# DistanceSensors.net
KiCad netlist of a schematic drawn in Altium Designer
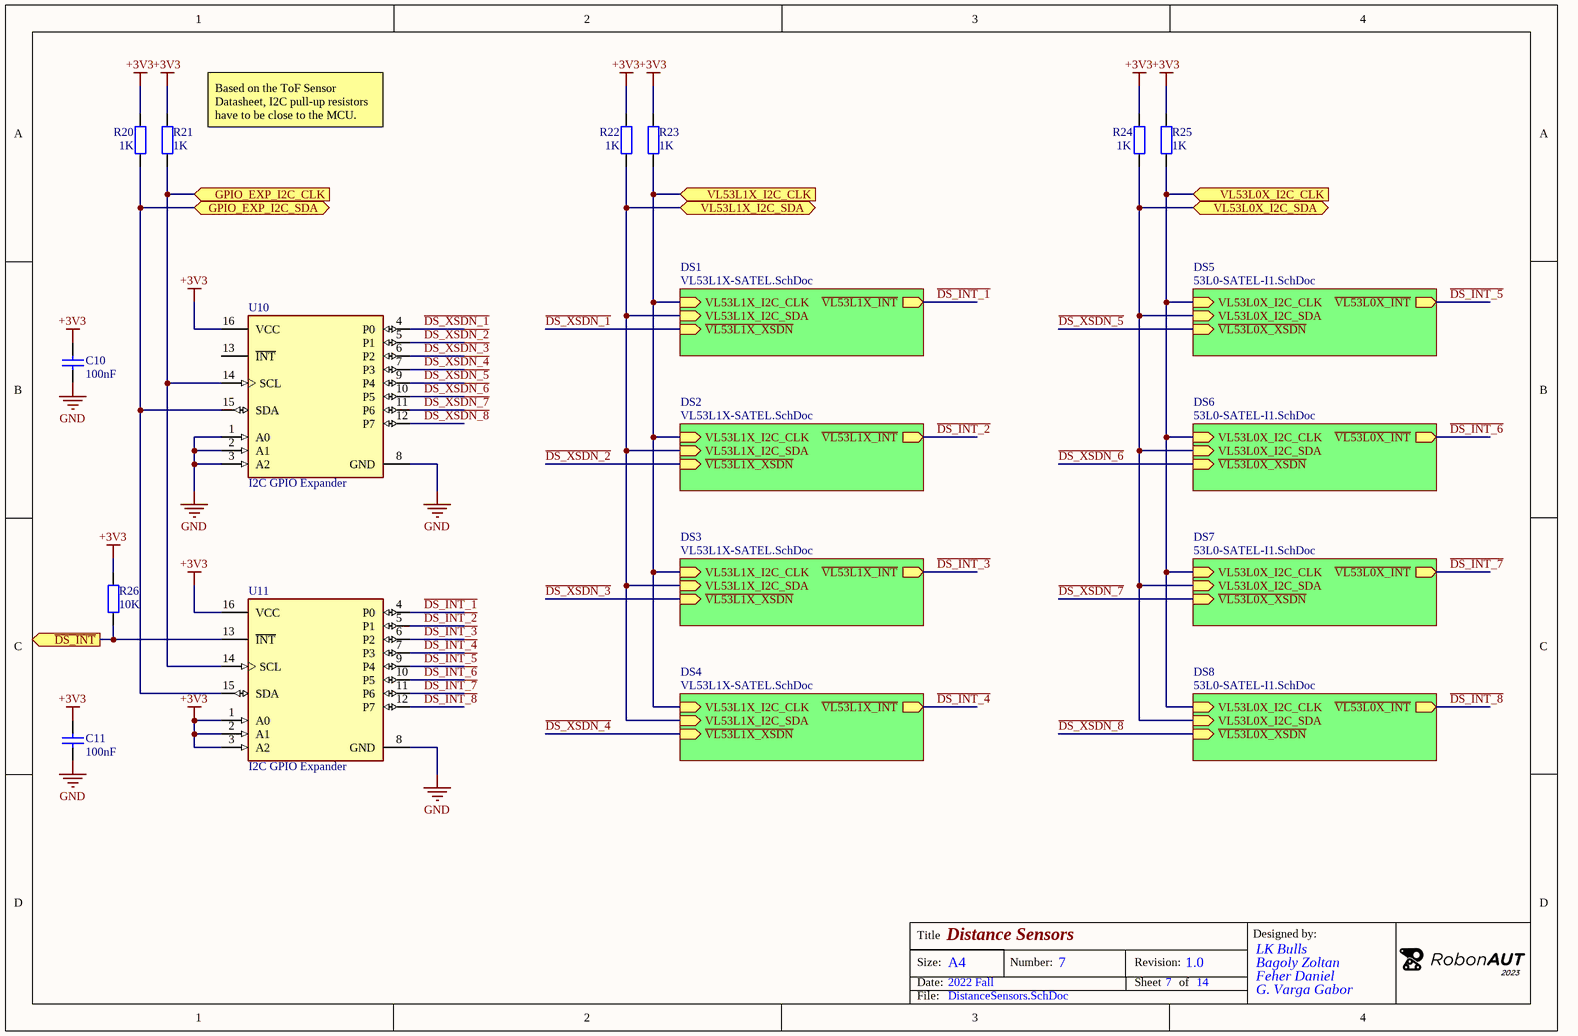
[diagram p0: DistanceSensors.SchDoc]

(export (version "E")
  (design (tool "Eeschema 10.0.6"))
  (components
    (comp (ref "C10")
      (value "100nF")
      (footprint "FP_0805_CAP_085")
      (description "Capacitor")
      (fields (field (name "TOLERANCE") "10%") (field (name "VOLTAGE") "50V"))
      (libsource (lib "LKBulls2023") (part "CAP"))
    )
    (comp (ref "C11")
      (value "100nF")
      (footprint "FP_0805_CAP_085")
      (description "Capacitor")
      (fields (field (name "TOLERANCE") "10%") (field (name "VOLTAGE") "50V"))
      (libsource (lib "LKBulls2023") (part "CAP"))
    )
    (comp (ref "R20")
      (value "1K")
      (footprint "FP_0805_RES")
      (description "Resistor")
      (fields (field (name "TOLERANCE") "5%") (field (name "POWER") "0.125W"))
      (libsource (lib "LKBulls2023") (part "RES"))
    )
    (comp (ref "R21")
      (value "1K")
      (footprint "FP_0805_RES")
      (description "Resistor")
      (fields (field (name "TOLERANCE") "5%") (field (name "POWER") "0.125W"))
      (libsource (lib "LKBulls2023") (part "RES"))
    )
    (comp (ref "R22")
      (value "1K")
      (footprint "FP_0805_RES")
      (description "Resistor")
      (fields (field (name "TOLERANCE") "5%") (field (name "POWER") "0.125W"))
      (libsource (lib "LKBulls2023") (part "RES"))
    )
    (comp (ref "R23")
      (value "1K")
      (footprint "FP_0805_RES")
      (description "Resistor")
      (fields (field (name "TOLERANCE") "5%") (field (name "POWER") "0.125W"))
      (libsource (lib "LKBulls2023") (part "RES"))
    )
    (comp (ref "R24")
      (value "1K")
      (footprint "FP_0805_RES")
      (description "Resistor")
      (fields (field (name "TOLERANCE") "5%") (field (name "POWER") "0.125W"))
      (libsource (lib "LKBulls2023") (part "RES"))
    )
    (comp (ref "R25")
      (value "1K")
      (footprint "FP_0805_RES")
      (description "Resistor")
      (fields (field (name "TOLERANCE") "5%") (field (name "POWER") "0.125W"))
      (libsource (lib "LKBulls2023") (part "RES"))
    )
    (comp (ref "R26")
      (value "10K")
      (footprint "FP_0805_RES")
      (description "Resistor")
      (fields (field (name "TOLERANCE") "5%") (field (name "POWER") "0.125W"))
      (libsource (lib "LKBulls2023") (part "RES"))
    )
    (comp (ref "U10")
      (value "I2C GPIO Expander")
      (footprint "FP_TCA9534PWR")
      (description "I2C/SMBus Interface 100kHz/400kHz 5.5V 16-Pin TSSOP T/R")
      (fields
        (field (name "MANUFACTURER") "Texas Instruments")
        (field (name "MANUFACTURER PART NUMBER") "TCA9534PWR")
      )
      (libsource (lib "LKBulls2023") (part "TCA9534PWR"))
    )
    (comp (ref "U11")
      (value "I2C GPIO Expander")
      (footprint "FP_TCA9534PWR")
      (description "I2C/SMBus Interface 100kHz/400kHz 5.5V 16-Pin TSSOP T/R")
      (fields
        (field (name "MANUFACTURER") "Texas Instruments")
        (field (name "MANUFACTURER PART NUMBER") "TCA9534PWR")
      )
      (libsource (lib "LKBulls2023") (part "TCA9534PWR"))
    )
  )
  (nets
    (net (code "1") (name "+3V3") (class "Default")
      (node (ref "C10") (pin "2") (pinfunction "2_2") (pintype "passive"))
      (node (ref "C11") (pin "2") (pinfunction "2_2") (pintype "passive"))
      (node (ref "R20") (pin "2") (pinfunction "2_2") (pintype "passive"))
      (node (ref "R21") (pin "2") (pinfunction "2_2") (pintype "passive"))
      (node (ref "R22") (pin "2") (pinfunction "2_2") (pintype "passive"))
      (node (ref "R23") (pin "2") (pinfunction "2_2") (pintype "passive"))
      (node (ref "R24") (pin "2") (pinfunction "2_2") (pintype "passive"))
      (node (ref "R25") (pin "2") (pinfunction "2_2") (pintype "passive"))
      (node (ref "R26") (pin "2") (pinfunction "2_2") (pintype "passive"))
      (node (ref "U10") (pin "16") (pinfunction "VCC_16") (pintype "power_in"))
      (node (ref "U11") (pin "1") (pinfunction "A0_1") (pintype "input"))
      (node (ref "U11") (pin "16") (pinfunction "VCC_16") (pintype "power_in"))
      (node (ref "U11") (pin "2") (pinfunction "A1_2") (pintype "input"))
      (node (ref "U11") (pin "3") (pinfunction "A2_3") (pintype "input"))
    )
    (net (code "2") (name "/GPIO_EXP_I2C_CLK") (class "Default")
      (node (ref "R21") (pin "1") (pinfunction "1_1") (pintype "passive"))
      (node (ref "U10") (pin "14") (pinfunction "SCL_14") (pintype "input"))
      (node (ref "U11") (pin "14") (pinfunction "SCL_14") (pintype "input"))
    )
    (net (code "3") (name "/GPIO_EXP_I2C_SDA") (class "Default")
      (node (ref "R20") (pin "1") (pinfunction "1_1") (pintype "passive"))
      (node (ref "U10") (pin "15") (pinfunction "SDA_15") (pintype "bidirectional"))
      (node (ref "U11") (pin "15") (pinfunction "SDA_15") (pintype "bidirectional"))
    )
    (net (code "4") (name "/VL53L0X_I2C_CLK") (class "Default")
      (node (ref "R25") (pin "1") (pinfunction "1_1") (pintype "passive"))
    )
    (net (code "5") (name "/VL53L0X_I2C_SDA") (class "Default")
      (node (ref "R24") (pin "1") (pinfunction "1_1") (pintype "passive"))
    )
    (net (code "6") (name "/VL53L1X_I2C_CLK") (class "Default")
      (node (ref "R23") (pin "1") (pinfunction "1_1") (pintype "passive"))
    )
    (net (code "7") (name "/VL53L1X_I2C_SDA") (class "Default")
      (node (ref "R22") (pin "1") (pinfunction "1_1") (pintype "passive"))
    )
    (net (code "8") (name "/~{DS_INT_1}") (class "Default")
      (node (ref "U11") (pin "4") (pinfunction "P0_4") (pintype "bidirectional"))
    )
    (net (code "9") (name "/~{DS_INT_2}") (class "Default")
      (node (ref "U11") (pin "5") (pinfunction "P1_5") (pintype "bidirectional"))
    )
    (net (code "10") (name "/~{DS_INT_3}") (class "Default")
      (node (ref "U11") (pin "6") (pinfunction "P2_6") (pintype "bidirectional"))
    )
    (net (code "11") (name "/~{DS_INT_4}") (class "Default")
      (node (ref "U11") (pin "7") (pinfunction "P3_7") (pintype "bidirectional"))
    )
    (net (code "12") (name "/~{DS_INT_5}") (class "Default")
      (node (ref "U11") (pin "9") (pinfunction "P4_9") (pintype "bidirectional"))
    )
    (net (code "13") (name "/~{DS_INT_6}") (class "Default")
      (node (ref "U11") (pin "10") (pinfunction "P5_10") (pintype "bidirectional"))
    )
    (net (code "14") (name "/~{DS_INT_7}") (class "Default")
      (node (ref "U11") (pin "11") (pinfunction "P6_11") (pintype "bidirectional"))
    )
    (net (code "15") (name "/~{DS_INT_8}") (class "Default")
      (node (ref "U11") (pin "12") (pinfunction "P7_12") (pintype "bidirectional"))
    )
    (net (code "16") (name "/~{DS_INT}") (class "Default")
      (node (ref "R26") (pin "1") (pinfunction "1_1") (pintype "passive"))
      (node (ref "U11") (pin "13") (pinfunction "~{INT}_13") (pintype "open_collector"))
    )
    (net (code "17") (name "/~{DS_XSDN_1}") (class "Default")
      (node (ref "U10") (pin "4") (pinfunction "P0_4") (pintype "bidirectional"))
    )
    (net (code "18") (name "/~{DS_XSDN_2}") (class "Default")
      (node (ref "U10") (pin "5") (pinfunction "P1_5") (pintype "bidirectional"))
    )
    (net (code "19") (name "/~{DS_XSDN_3}") (class "Default")
      (node (ref "U10") (pin "6") (pinfunction "P2_6") (pintype "bidirectional"))
    )
    (net (code "20") (name "/~{DS_XSDN_4}") (class "Default")
      (node (ref "U10") (pin "7") (pinfunction "P3_7") (pintype "bidirectional"))
    )
    (net (code "21") (name "/~{DS_XSDN_5}") (class "Default")
      (node (ref "U10") (pin "9") (pinfunction "P4_9") (pintype "bidirectional"))
    )
    (net (code "22") (name "/~{DS_XSDN_6}") (class "Default")
      (node (ref "U10") (pin "10") (pinfunction "P5_10") (pintype "bidirectional"))
    )
    (net (code "23") (name "/~{DS_XSDN_7}") (class "Default")
      (node (ref "U10") (pin "11") (pinfunction "P6_11") (pintype "bidirectional"))
    )
    (net (code "24") (name "/~{DS_XSDN_8}") (class "Default")
      (node (ref "U10") (pin "12") (pinfunction "P7_12") (pintype "bidirectional"))
    )
    (net (code "25") (name "GND") (class "Default")
      (node (ref "C10") (pin "1") (pinfunction "1_1") (pintype "passive"))
      (node (ref "C11") (pin "1") (pinfunction "1_1") (pintype "passive"))
      (node (ref "U10") (pin "1") (pinfunction "A0_1") (pintype "input"))
      (node (ref "U10") (pin "2") (pinfunction "A1_2") (pintype "input"))
      (node (ref "U10") (pin "3") (pinfunction "A2_3") (pintype "input"))
      (node (ref "U10") (pin "8") (pinfunction "GND_8") (pintype "power_in"))
      (node (ref "U11") (pin "8") (pinfunction "GND_8") (pintype "power_in"))
    )
    (net (code "26") (name "unconnected-(U10-~{INT}-Pad13)") (class "Default")
      (node (ref "U10") (pin "13") (pinfunction "~{INT}_13") (pintype "open_collector"))
    )
  )
)
